# sesam_v2.net
KiCad netlist of a schematic drawn in EAGLE
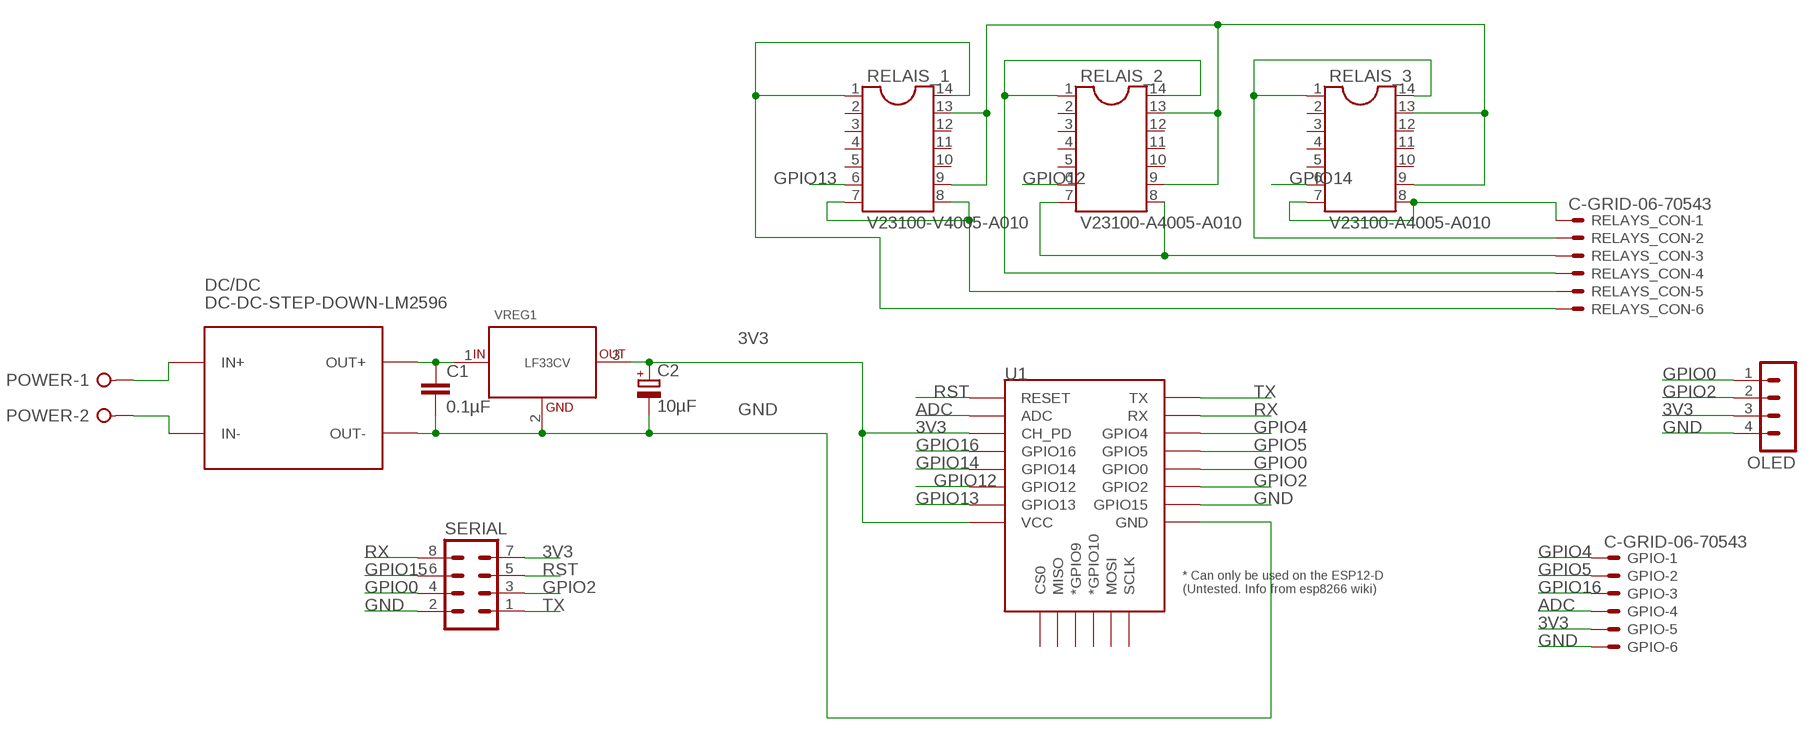
[diagram p0: schematic, sheet 1]

(export (version "E")
  (design (tool "Eeschema 10.0.6"))
  (components
    (comp (ref "C1")
      (value "0.1µF")
      (footprint "eagle-import:C0805")
      (libsource (lib "eagle-import") (part "C-EUC0805"))
    )
    (comp (ref "C2")
      (value "10µF")
      (footprint "eagle-import:E2-5")
      (libsource (lib "eagle-import") (part "CPOL-EUE2-5"))
    )
    (comp (ref "DC/DC")
      (value "DC-DC-STEP-DOWN-LM2596")
      (footprint "eagle-import:DC-DC-STEP-DOWN-LM2596")
      (libsource (lib "eagle-import") (part "DC-DC-STEP-DOWN-LM2596"))
    )
    (comp (ref "GPIO")
      (value "C-GRID-06-70543")
      (footprint "eagle-import:70543-06")
      (libsource (lib "eagle-import") (part "C-GRID-06-70543"))
    )
    (comp (ref "OLED")
      (value "MA04-1")
      (footprint "eagle-import:MA04-1")
      (libsource (lib "eagle-import") (part "MA04-1"))
    )
    (comp (ref "POWER")
      (value "W237-02P")
      (footprint "eagle-import:W237-132")
      (libsource (lib "eagle-import") (part "W237-02P"))
    )
    (comp (ref "RELAIS_1")
      (value "V23100-V4005-A010")
      (footprint "eagle-import:SOCKET-14")
      (libsource (lib "eagle-import") (part "DIL14S"))
    )
    (comp (ref "RELAIS_2")
      (value "V23100-A4005-A010")
      (footprint "eagle-import:SOCKET-14")
      (libsource (lib "eagle-import") (part "DIL14S"))
    )
    (comp (ref "RELAIS_3")
      (value "V23100-A4005-A010")
      (footprint "eagle-import:SOCKET-14")
      (libsource (lib "eagle-import") (part "DIL14S"))
    )
    (comp (ref "RELAYS_CON")
      (value "C-GRID-06-70543")
      (footprint "eagle-import:70543-06")
      (libsource (lib "eagle-import") (part "C-GRID-06-70543"))
    )
    (comp (ref "SERIAL")
      (value "MA04-2")
      (footprint "eagle-import:MA04-2")
      (libsource (lib "eagle-import") (part "MA04-2"))
    )
    (comp (ref "U1")
      (value "ESP12ESMD")
      (footprint "eagle-import:ESP12E-SMD")
      (libsource (lib "eagle-import") (part "ESP12ESMD"))
    )
    (comp (ref "VREG1")
      (value "LF33CV")
      (footprint "eagle-import:TO220")
      (libsource (lib "eagle-import") (part "LF33CV"))
    )
  )
  (nets
    (net (code "1") (name "/3V3") (class "Default")
      (node (ref "C2") (pin "+") (pinfunction "+_+") (pintype "passive"))
      (node (ref "GPIO") (pin "5") (pinfunction "S_5") (pintype "passive"))
      (node (ref "OLED") (pin "3") (pinfunction "3_3") (pintype "passive"))
      (node (ref "SERIAL") (pin "7") (pinfunction "7_7") (pintype "passive"))
      (node (ref "U1") (pin "CH_PD") (pinfunction "CH_PD_CH_PD") (pintype "bidirectional"))
      (node (ref "U1") (pin "VCC") (pinfunction "VCC_VCC") (pintype "bidirectional"))
      (node (ref "VREG1") (pin "3") (pinfunction "OUT_3") (pintype "output"))
    )
    (net (code "2") (name "/ADC") (class "Default")
      (node (ref "GPIO") (pin "4") (pinfunction "S_4") (pintype "passive"))
      (node (ref "U1") (pin "ADC") (pinfunction "ADC_ADC") (pintype "bidirectional"))
    )
    (net (code "3") (name "/GND") (class "Default")
      (node (ref "C1") (pin "2") (pinfunction "2_2") (pintype "passive"))
      (node (ref "C2") (pin "-") (pinfunction "-_-") (pintype "passive"))
      (node (ref "DC/DC") (pin "IN-") (pinfunction "IN-_IN-") (pintype "bidirectional"))
      (node (ref "DC/DC") (pin "OUT-") (pinfunction "OUT-_OUT-") (pintype "bidirectional"))
      (node (ref "GPIO") (pin "6") (pinfunction "S_6") (pintype "passive"))
      (node (ref "OLED") (pin "4") (pinfunction "4_4") (pintype "passive"))
      (node (ref "POWER") (pin "2") (pinfunction "KL_2") (pintype "passive"))
      (node (ref "RELAIS_1") (pin "13") (pinfunction "13_13") (pintype "passive"))
      (node (ref "RELAIS_1") (pin "9") (pinfunction "9_9") (pintype "passive"))
      (node (ref "RELAIS_2") (pin "13") (pinfunction "13_13") (pintype "passive"))
      (node (ref "RELAIS_2") (pin "9") (pinfunction "9_9") (pintype "passive"))
      (node (ref "RELAIS_3") (pin "13") (pinfunction "13_13") (pintype "passive"))
      (node (ref "RELAIS_3") (pin "9") (pinfunction "9_9") (pintype "passive"))
      (node (ref "SERIAL") (pin "2") (pinfunction "2_2") (pintype "passive"))
      (node (ref "U1") (pin "GND") (pinfunction "GND_GND") (pintype "bidirectional"))
      (node (ref "U1") (pin "GPIO15") (pinfunction "GPIO15_GPIO15") (pintype "bidirectional"))
      (node (ref "VREG1") (pin "2") (pinfunction "GND_2") (pintype "input"))
    )
    (net (code "4") (name "/GPIO0") (class "Default")
      (node (ref "OLED") (pin "1") (pinfunction "1_1") (pintype "passive"))
      (node (ref "SERIAL") (pin "4") (pinfunction "4_4") (pintype "passive"))
      (node (ref "U1") (pin "GPIO0") (pinfunction "GPIO0_GPIO0") (pintype "bidirectional"))
    )
    (net (code "5") (name "/GPIO2") (class "Default")
      (node (ref "OLED") (pin "2") (pinfunction "2_2") (pintype "passive"))
      (node (ref "SERIAL") (pin "3") (pinfunction "3_3") (pintype "passive"))
      (node (ref "U1") (pin "GPIO2") (pinfunction "GPIO2_GPIO2") (pintype "bidirectional"))
    )
    (net (code "6") (name "/GPIO4") (class "Default")
      (node (ref "GPIO") (pin "1") (pinfunction "S_1") (pintype "passive"))
      (node (ref "U1") (pin "GPIO4") (pinfunction "GPIO4_GPIO4") (pintype "bidirectional"))
    )
    (net (code "7") (name "/GPIO5") (class "Default")
      (node (ref "GPIO") (pin "2") (pinfunction "S_2") (pintype "passive"))
      (node (ref "U1") (pin "GPIO5") (pinfunction "GPIO5_GPIO5") (pintype "bidirectional"))
    )
    (net (code "8") (name "/GPIO12") (class "Default")
      (node (ref "RELAIS_2") (pin "6") (pinfunction "6_6") (pintype "passive"))
      (node (ref "U1") (pin "GPIO12") (pinfunction "GPIO12_GPIO12") (pintype "bidirectional"))
    )
    (net (code "9") (name "/GPIO13") (class "Default")
      (node (ref "RELAIS_1") (pin "6") (pinfunction "6_6") (pintype "passive"))
      (node (ref "U1") (pin "GPIO13") (pinfunction "GPIO13_GPIO13") (pintype "bidirectional"))
    )
    (net (code "10") (name "/GPIO14") (class "Default")
      (node (ref "RELAIS_3") (pin "6") (pinfunction "6_6") (pintype "passive"))
      (node (ref "U1") (pin "GPIO14") (pinfunction "GPIO14_GPIO14") (pintype "bidirectional"))
    )
    (net (code "11") (name "/GPIO15") (class "Default")
      (node (ref "SERIAL") (pin "6") (pinfunction "6_6") (pintype "passive"))
    )
    (net (code "12") (name "/GPIO16") (class "Default")
      (node (ref "GPIO") (pin "3") (pinfunction "S_3") (pintype "passive"))
      (node (ref "U1") (pin "GPIO16") (pinfunction "GPIO16_GPIO16") (pintype "bidirectional"))
    )
    (net (code "13") (name "/RST") (class "Default")
      (node (ref "SERIAL") (pin "5") (pinfunction "5_5") (pintype "passive"))
      (node (ref "U1") (pin "RESET") (pinfunction "RESET_RESET") (pintype "bidirectional"))
    )
    (net (code "14") (name "/RX") (class "Default")
      (node (ref "SERIAL") (pin "8") (pinfunction "8_8") (pintype "passive"))
      (node (ref "U1") (pin "RXD0") (pinfunction "RX_RXD0") (pintype "bidirectional"))
    )
    (net (code "15") (name "/TX") (class "Default")
      (node (ref "SERIAL") (pin "1") (pinfunction "1_1") (pintype "passive"))
      (node (ref "U1") (pin "TXD0") (pinfunction "TX_TXD0") (pintype "bidirectional"))
    )
    (net (code "16") (name "Net-(POWERA-KL)") (class "Default")
      (node (ref "DC/DC") (pin "IN+") (pinfunction "IN+_IN+") (pintype "bidirectional"))
      (node (ref "POWER") (pin "1") (pinfunction "KL_1") (pintype "passive"))
    )
    (net (code "17") (name "Net-(RELAYS_CONA-S)") (class "Default")
      (node (ref "RELAIS_3") (pin "7") (pinfunction "7_7") (pintype "passive"))
      (node (ref "RELAIS_3") (pin "8") (pinfunction "8_8") (pintype "passive"))
      (node (ref "RELAYS_CON") (pin "1") (pinfunction "S_1") (pintype "passive"))
    )
    (net (code "18") (name "Net-(RELAYS_CONB-S)") (class "Default")
      (node (ref "RELAIS_3") (pin "1") (pinfunction "1_1") (pintype "passive"))
      (node (ref "RELAIS_3") (pin "14") (pinfunction "14_14") (pintype "passive"))
      (node (ref "RELAYS_CON") (pin "2") (pinfunction "S_2") (pintype "passive"))
    )
    (net (code "19") (name "Net-(RELAYS_CONC-S)") (class "Default")
      (node (ref "RELAIS_2") (pin "7") (pinfunction "7_7") (pintype "passive"))
      (node (ref "RELAIS_2") (pin "8") (pinfunction "8_8") (pintype "passive"))
      (node (ref "RELAYS_CON") (pin "3") (pinfunction "S_3") (pintype "passive"))
    )
    (net (code "20") (name "Net-(RELAYS_COND-S)") (class "Default")
      (node (ref "RELAIS_2") (pin "1") (pinfunction "1_1") (pintype "passive"))
      (node (ref "RELAIS_2") (pin "14") (pinfunction "14_14") (pintype "passive"))
      (node (ref "RELAYS_CON") (pin "4") (pinfunction "S_4") (pintype "passive"))
    )
    (net (code "21") (name "Net-(RELAYS_CONE-S)") (class "Default")
      (node (ref "RELAIS_1") (pin "7") (pinfunction "7_7") (pintype "passive"))
      (node (ref "RELAIS_1") (pin "8") (pinfunction "8_8") (pintype "passive"))
      (node (ref "RELAYS_CON") (pin "5") (pinfunction "S_5") (pintype "passive"))
    )
    (net (code "22") (name "Net-(RELAYS_CONF-S)") (class "Default")
      (node (ref "RELAIS_1") (pin "1") (pinfunction "1_1") (pintype "passive"))
      (node (ref "RELAIS_1") (pin "14") (pinfunction "14_14") (pintype "passive"))
      (node (ref "RELAYS_CON") (pin "6") (pinfunction "S_6") (pintype "passive"))
    )
    (net (code "23") (name "Net-(VREG1-IN)") (class "Default")
      (node (ref "C1") (pin "1") (pinfunction "1_1") (pintype "passive"))
      (node (ref "DC/DC") (pin "OUT+") (pinfunction "OUT+_OUT+") (pintype "bidirectional"))
      (node (ref "VREG1") (pin "1") (pinfunction "IN_1") (pintype "input"))
    )
    (net (code "24") (name "unconnected-(RELAIS_1-Pad2)") (class "Default")
      (node (ref "RELAIS_1") (pin "2") (pinfunction "2_2") (pintype "passive"))
    )
    (net (code "25") (name "unconnected-(RELAIS_1-Pad3)") (class "Default")
      (node (ref "RELAIS_1") (pin "3") (pinfunction "3_3") (pintype "passive"))
    )
    (net (code "26") (name "unconnected-(RELAIS_1-Pad4)") (class "Default")
      (node (ref "RELAIS_1") (pin "4") (pinfunction "4_4") (pintype "passive"))
    )
    (net (code "27") (name "unconnected-(RELAIS_1-Pad5)") (class "Default")
      (node (ref "RELAIS_1") (pin "5") (pinfunction "5_5") (pintype "passive"))
    )
    (net (code "28") (name "unconnected-(RELAIS_1-Pad10)") (class "Default")
      (node (ref "RELAIS_1") (pin "10") (pinfunction "10_10") (pintype "passive"))
    )
    (net (code "29") (name "unconnected-(RELAIS_1-Pad11)") (class "Default")
      (node (ref "RELAIS_1") (pin "11") (pinfunction "11_11") (pintype "passive"))
    )
    (net (code "30") (name "unconnected-(RELAIS_1-Pad12)") (class "Default")
      (node (ref "RELAIS_1") (pin "12") (pinfunction "12_12") (pintype "passive"))
    )
    (net (code "31") (name "unconnected-(RELAIS_2-Pad2)") (class "Default")
      (node (ref "RELAIS_2") (pin "2") (pinfunction "2_2") (pintype "passive"))
    )
    (net (code "32") (name "unconnected-(RELAIS_2-Pad3)") (class "Default")
      (node (ref "RELAIS_2") (pin "3") (pinfunction "3_3") (pintype "passive"))
    )
    (net (code "33") (name "unconnected-(RELAIS_2-Pad4)") (class "Default")
      (node (ref "RELAIS_2") (pin "4") (pinfunction "4_4") (pintype "passive"))
    )
    (net (code "34") (name "unconnected-(RELAIS_2-Pad5)") (class "Default")
      (node (ref "RELAIS_2") (pin "5") (pinfunction "5_5") (pintype "passive"))
    )
    (net (code "35") (name "unconnected-(RELAIS_2-Pad10)") (class "Default")
      (node (ref "RELAIS_2") (pin "10") (pinfunction "10_10") (pintype "passive"))
    )
    (net (code "36") (name "unconnected-(RELAIS_2-Pad11)") (class "Default")
      (node (ref "RELAIS_2") (pin "11") (pinfunction "11_11") (pintype "passive"))
    )
    (net (code "37") (name "unconnected-(RELAIS_2-Pad12)") (class "Default")
      (node (ref "RELAIS_2") (pin "12") (pinfunction "12_12") (pintype "passive"))
    )
    (net (code "38") (name "unconnected-(RELAIS_3-Pad2)") (class "Default")
      (node (ref "RELAIS_3") (pin "2") (pinfunction "2_2") (pintype "passive"))
    )
    (net (code "39") (name "unconnected-(RELAIS_3-Pad3)") (class "Default")
      (node (ref "RELAIS_3") (pin "3") (pinfunction "3_3") (pintype "passive"))
    )
    (net (code "40") (name "unconnected-(RELAIS_3-Pad4)") (class "Default")
      (node (ref "RELAIS_3") (pin "4") (pinfunction "4_4") (pintype "passive"))
    )
    (net (code "41") (name "unconnected-(RELAIS_3-Pad5)") (class "Default")
      (node (ref "RELAIS_3") (pin "5") (pinfunction "5_5") (pintype "passive"))
    )
    (net (code "42") (name "unconnected-(RELAIS_3-Pad10)") (class "Default")
      (node (ref "RELAIS_3") (pin "10") (pinfunction "10_10") (pintype "passive"))
    )
    (net (code "43") (name "unconnected-(RELAIS_3-Pad11)") (class "Default")
      (node (ref "RELAIS_3") (pin "11") (pinfunction "11_11") (pintype "passive"))
    )
    (net (code "44") (name "unconnected-(RELAIS_3-Pad12)") (class "Default")
      (node (ref "RELAIS_3") (pin "12") (pinfunction "12_12") (pintype "passive"))
    )
    (net (code "45") (name "unconnected-(U1-*GPIO9-PadGPIO9)") (class "Default")
      (node (ref "U1") (pin "GPIO9") (pinfunction "*GPIO9_GPIO9") (pintype "bidirectional"))
    )
    (net (code "46") (name "unconnected-(U1-*GPIO10-PadGPIO10)") (class "Default")
      (node (ref "U1") (pin "GPIO10") (pinfunction "*GPIO10_GPIO10") (pintype "bidirectional"))
    )
    (net (code "47") (name "unconnected-(U1-PadCS0)") (class "Default")
      (node (ref "U1") (pin "CS0") (pinfunction "CS0_CS0") (pintype "bidirectional"))
    )
    (net (code "48") (name "unconnected-(U1-PadMISO)") (class "Default")
      (node (ref "U1") (pin "MISO") (pinfunction "MISO_MISO") (pintype "bidirectional"))
    )
    (net (code "49") (name "unconnected-(U1-PadMOSI)") (class "Default")
      (node (ref "U1") (pin "MOSI") (pinfunction "MOSI_MOSI") (pintype "bidirectional"))
    )
    (net (code "50") (name "unconnected-(U1-PadSCLK)") (class "Default")
      (node (ref "U1") (pin "SCLK") (pinfunction "SCLK_SCLK") (pintype "bidirectional"))
    )
  )
)
